# Top.net
KiCad netlist of a schematic drawn in Altium Designer
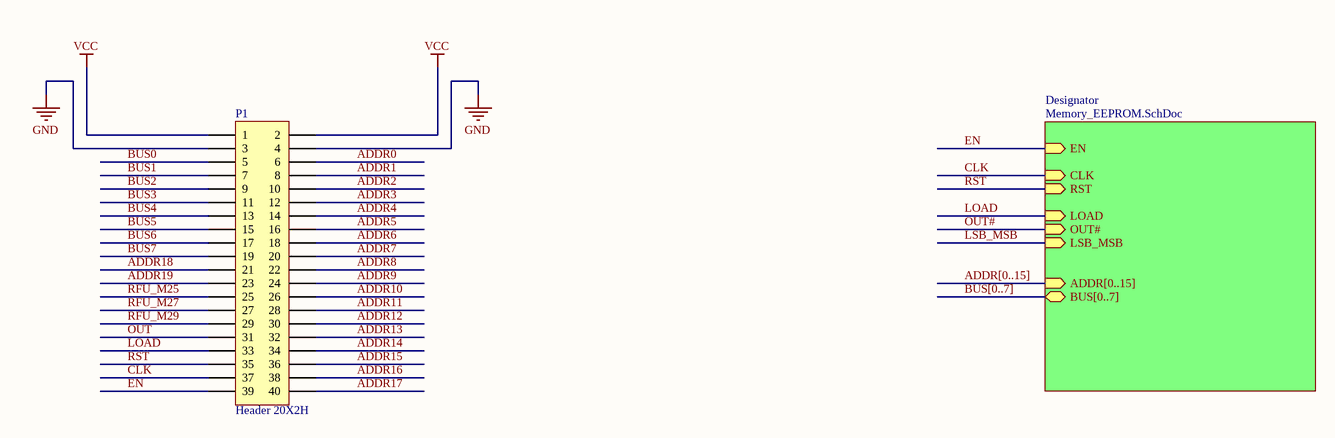
[diagram p0: Top.SchDoc]

(export (version "E")
  (design (tool "Eeschema 10.0.6"))
  (components
    (comp (ref "P1")
      (value "Header 20X2H")
      (footprint "HDR2X20H")
      (description "Header, 20-Pin, Dual row, Right Angle")
      (fields (field (name "PUBLISHER") "Altium Limited"))
      (libsource (lib "Miscellaneous Connectors") (part "Header 20X2H"))
    )
  )
  (nets
    (net (code "1") (name "/ADDR0") (class "Default")
      (node (ref "P1") (pin "6") (pinfunction "6_6") (pintype "passive"))
    )
    (net (code "2") (name "/ADDR1") (class "Default")
      (node (ref "P1") (pin "8") (pinfunction "8_8") (pintype "passive"))
    )
    (net (code "3") (name "/ADDR2") (class "Default")
      (node (ref "P1") (pin "10") (pinfunction "10_10") (pintype "passive"))
    )
    (net (code "4") (name "/ADDR3") (class "Default")
      (node (ref "P1") (pin "12") (pinfunction "12_12") (pintype "passive"))
    )
    (net (code "5") (name "/ADDR4") (class "Default")
      (node (ref "P1") (pin "14") (pinfunction "14_14") (pintype "passive"))
    )
    (net (code "6") (name "/ADDR5") (class "Default")
      (node (ref "P1") (pin "16") (pinfunction "16_16") (pintype "passive"))
    )
    (net (code "7") (name "/ADDR6") (class "Default")
      (node (ref "P1") (pin "18") (pinfunction "18_18") (pintype "passive"))
    )
    (net (code "8") (name "/ADDR7") (class "Default")
      (node (ref "P1") (pin "20") (pinfunction "20_20") (pintype "passive"))
    )
    (net (code "9") (name "/ADDR8") (class "Default")
      (node (ref "P1") (pin "22") (pinfunction "22_22") (pintype "passive"))
    )
    (net (code "10") (name "/ADDR9") (class "Default")
      (node (ref "P1") (pin "24") (pinfunction "24_24") (pintype "passive"))
    )
    (net (code "11") (name "/ADDR10") (class "Default")
      (node (ref "P1") (pin "26") (pinfunction "26_26") (pintype "passive"))
    )
    (net (code "12") (name "/ADDR11") (class "Default")
      (node (ref "P1") (pin "28") (pinfunction "28_28") (pintype "passive"))
    )
    (net (code "13") (name "/ADDR12") (class "Default")
      (node (ref "P1") (pin "30") (pinfunction "30_30") (pintype "passive"))
    )
    (net (code "14") (name "/ADDR13") (class "Default")
      (node (ref "P1") (pin "32") (pinfunction "32_32") (pintype "passive"))
    )
    (net (code "15") (name "/ADDR14") (class "Default")
      (node (ref "P1") (pin "34") (pinfunction "34_34") (pintype "passive"))
    )
    (net (code "16") (name "/ADDR15") (class "Default")
      (node (ref "P1") (pin "36") (pinfunction "36_36") (pintype "passive"))
    )
    (net (code "17") (name "/ADDR16") (class "Default")
      (node (ref "P1") (pin "38") (pinfunction "38_38") (pintype "passive"))
    )
    (net (code "18") (name "/ADDR17") (class "Default")
      (node (ref "P1") (pin "40") (pinfunction "40_40") (pintype "passive"))
    )
    (net (code "19") (name "/ADDR18") (class "Default")
      (node (ref "P1") (pin "21") (pinfunction "21_21") (pintype "passive"))
    )
    (net (code "20") (name "/ADDR19") (class "Default")
      (node (ref "P1") (pin "23") (pinfunction "23_23") (pintype "passive"))
    )
    (net (code "22") (name "/BUS0") (class "Default")
      (node (ref "P1") (pin "5") (pinfunction "5_5") (pintype "passive"))
    )
    (net (code "23") (name "/BUS1") (class "Default")
      (node (ref "P1") (pin "7") (pinfunction "7_7") (pintype "passive"))
    )
    (net (code "24") (name "/BUS2") (class "Default")
      (node (ref "P1") (pin "9") (pinfunction "9_9") (pintype "passive"))
    )
    (net (code "25") (name "/BUS3") (class "Default")
      (node (ref "P1") (pin "11") (pinfunction "11_11") (pintype "passive"))
    )
    (net (code "26") (name "/BUS4") (class "Default")
      (node (ref "P1") (pin "13") (pinfunction "13_13") (pintype "passive"))
    )
    (net (code "27") (name "/BUS5") (class "Default")
      (node (ref "P1") (pin "15") (pinfunction "15_15") (pintype "passive"))
    )
    (net (code "28") (name "/BUS6") (class "Default")
      (node (ref "P1") (pin "17") (pinfunction "17_17") (pintype "passive"))
    )
    (net (code "29") (name "/BUS7") (class "Default")
      (node (ref "P1") (pin "19") (pinfunction "19_19") (pintype "passive"))
    )
    (net (code "31") (name "/CLK") (class "Default")
      (node (ref "P1") (pin "37") (pinfunction "37_37") (pintype "passive"))
    )
    (net (code "32") (name "/EN") (class "Default")
      (node (ref "P1") (pin "39") (pinfunction "39_39") (pintype "passive"))
    )
    (net (code "33") (name "/LOAD") (class "Default")
      (node (ref "P1") (pin "33") (pinfunction "33_33") (pintype "passive"))
    )
    (net (code "36") (name "/RFU_M25") (class "Default")
      (node (ref "P1") (pin "25") (pinfunction "25_25") (pintype "passive"))
    )
    (net (code "37") (name "/RFU_M27") (class "Default")
      (node (ref "P1") (pin "27") (pinfunction "27_27") (pintype "passive"))
    )
    (net (code "38") (name "/RFU_M29") (class "Default")
      (node (ref "P1") (pin "29") (pinfunction "29_29") (pintype "passive"))
    )
    (net (code "39") (name "/RST") (class "Default")
      (node (ref "P1") (pin "35") (pinfunction "35_35") (pintype "passive"))
    )
    (net (code "40") (name "/~{OUT}") (class "Default")
      (node (ref "P1") (pin "31") (pinfunction "31_31") (pintype "passive"))
    )
    (net (code "41") (name "GND") (class "Default")
      (node (ref "P1") (pin "3") (pinfunction "3_3") (pintype "passive"))
      (node (ref "P1") (pin "4") (pinfunction "4_4") (pintype "passive"))
    )
    (net (code "42") (name "VCC") (class "Default")
      (node (ref "P1") (pin "1") (pinfunction "1_1") (pintype "passive"))
      (node (ref "P1") (pin "2") (pinfunction "2_2") (pintype "passive"))
    )
  )
)
